# GT_pos_router.net
KiCad netlist of a schematic drawn in EAGLE
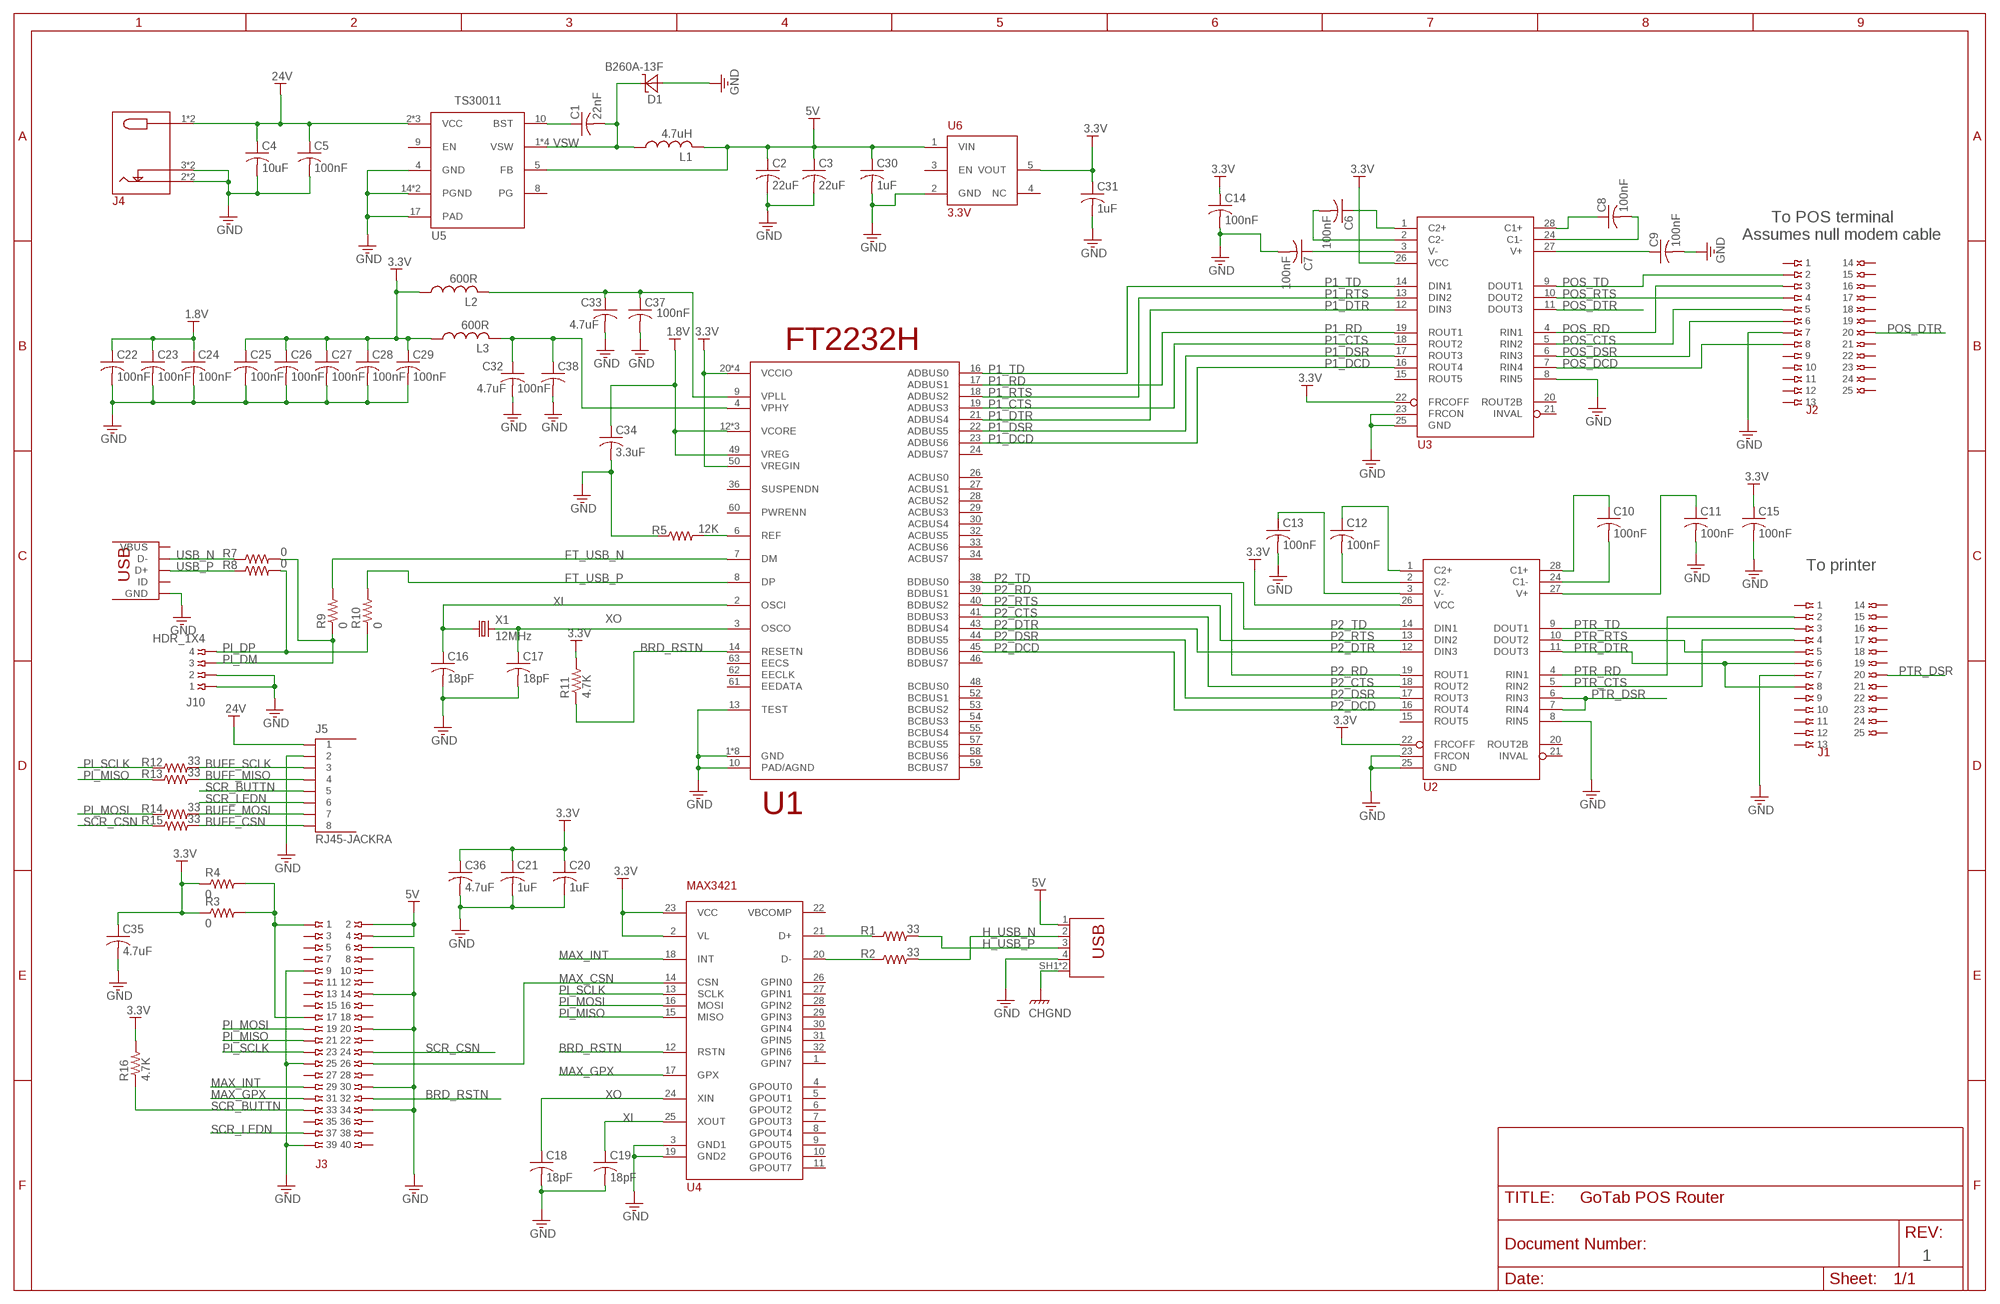
[diagram p0: schematic, sheet 1]

(export (version "E")
  (design (tool "Eeschema 10.0.6"))
  (components
    (comp (ref "C1")
      (value "22nF")
      (footprint "eagle-import:CAPC100X50X55L25N")
      (fields (field (name "VOLTAGE") "16V"))
      (libsource (lib "eagle-import") (part "C0402-22NF-16V-10-X7R"))
    )
    (comp (ref "C2")
      (value "22uF")
      (footprint "eagle-import:CAPC3216X85L50N")
      (fields (field (name "VOLTAGE") "25V"))
      (libsource (lib "eagle-import") (part "C1206-22UF-25V-20-X5R"))
    )
    (comp (ref "C3")
      (value "22uF")
      (footprint "eagle-import:CAPC3216X85L50N")
      (fields (field (name "VOLTAGE") "25V"))
      (libsource (lib "eagle-import") (part "C1206-22UF-25V-20-X5R"))
    )
    (comp (ref "C4")
      (value "10uF")
      (footprint "eagle-import:CAPC3216X85L50N")
      (fields (field (name "VOLTAGE") "35V"))
      (libsource (lib "eagle-import") (part "C1206-10UF-35V-10-X5R"))
    )
    (comp (ref "C5")
      (value "100nF")
      (footprint "eagle-import:CAPC1608X87L35N")
      (fields (field (name "VOLTAGE") "50V"))
      (libsource (lib "eagle-import") (part "C0603-100NF-50V-5-X7R"))
    )
    (comp (ref "C6")
      (value "100nF")
      (footprint "eagle-import:CAPC1608X87L35N")
      (fields (field (name "VOLTAGE") "50V"))
      (libsource (lib "eagle-import") (part "C0603-100NF-50V-5-X7R"))
    )
    (comp (ref "C7")
      (value "100nF")
      (footprint "eagle-import:CAPC1608X87L35N")
      (fields (field (name "VOLTAGE") "50V"))
      (libsource (lib "eagle-import") (part "C0603-100NF-50V-5-X7R"))
    )
    (comp (ref "C8")
      (value "100nF")
      (footprint "eagle-import:CAPC1608X87L35N")
      (fields (field (name "VOLTAGE") "50V"))
      (libsource (lib "eagle-import") (part "C0603-100NF-50V-5-X7R"))
    )
    (comp (ref "C9")
      (value "100nF")
      (footprint "eagle-import:CAPC1608X87L35N")
      (fields (field (name "VOLTAGE") "50V"))
      (libsource (lib "eagle-import") (part "C0603-100NF-50V-5-X7R"))
    )
    (comp (ref "C10")
      (value "100nF")
      (footprint "eagle-import:CAPC1608X87L35N")
      (fields (field (name "VOLTAGE") "50V"))
      (libsource (lib "eagle-import") (part "C0603-100NF-50V-5-X7R"))
    )
    (comp (ref "C11")
      (value "100nF")
      (footprint "eagle-import:CAPC1608X87L35N")
      (fields (field (name "VOLTAGE") "50V"))
      (libsource (lib "eagle-import") (part "C0603-100NF-50V-5-X7R"))
    )
    (comp (ref "C12")
      (value "100nF")
      (footprint "eagle-import:CAPC1608X87L35N")
      (fields (field (name "VOLTAGE") "50V"))
      (libsource (lib "eagle-import") (part "C0603-100NF-50V-5-X7R"))
    )
    (comp (ref "C13")
      (value "100nF")
      (footprint "eagle-import:CAPC1608X87L35N")
      (fields (field (name "VOLTAGE") "50V"))
      (libsource (lib "eagle-import") (part "C0603-100NF-50V-5-X7R"))
    )
    (comp (ref "C14")
      (value "100nF")
      (footprint "eagle-import:CAPC1608X87L35N")
      (fields (field (name "VOLTAGE") "50V"))
      (libsource (lib "eagle-import") (part "C0603-100NF-50V-5-X7R"))
    )
    (comp (ref "C15")
      (value "100nF")
      (footprint "eagle-import:CAPC1608X87L35N")
      (fields (field (name "VOLTAGE") "50V"))
      (libsource (lib "eagle-import") (part "C0603-100NF-50V-5-X7R"))
    )
    (comp (ref "C16")
      (value "18pF")
      (footprint "eagle-import:CAPC100X50X55L25N")
      (fields (field (name "VOLTAGE") "50V"))
      (libsource (lib "eagle-import") (part "C0402-18PF-50V-5-NPO"))
    )
    (comp (ref "C17")
      (value "18pF")
      (footprint "eagle-import:CAPC100X50X55L25N")
      (fields (field (name "VOLTAGE") "50V"))
      (libsource (lib "eagle-import") (part "C0402-18PF-50V-5-NPO"))
    )
    (comp (ref "C18")
      (value "18pF")
      (footprint "eagle-import:CAPC100X50X55L25N")
      (fields (field (name "VOLTAGE") "50V"))
      (libsource (lib "eagle-import") (part "C0402-18PF-50V-5-NPO"))
    )
    (comp (ref "C19")
      (value "18pF")
      (footprint "eagle-import:CAPC100X50X55L25N")
      (fields (field (name "VOLTAGE") "50V"))
      (libsource (lib "eagle-import") (part "C0402-18PF-50V-5-NPO"))
    )
    (comp (ref "C20")
      (value "1uF")
      (footprint "eagle-import:CAPC1608X87L35N")
      (fields (field (name "VOLTAGE") "16V"))
      (libsource (lib "eagle-import") (part "C0603-1UF-16V-10-X7R"))
    )
    (comp (ref "C21")
      (value "1uF")
      (footprint "eagle-import:CAPC1608X87L35N")
      (fields (field (name "VOLTAGE") "16V"))
      (libsource (lib "eagle-import") (part "C0603-1UF-16V-10-X7R"))
    )
    (comp (ref "C22")
      (value "100nF")
      (footprint "eagle-import:CAPC100X50X55L25N")
      (fields (field (name "VOLTAGE") "16V"))
      (libsource (lib "eagle-import") (part "C0402-100NF-16V-10-X7R"))
    )
    (comp (ref "C23")
      (value "100nF")
      (footprint "eagle-import:CAPC100X50X55L25N")
      (fields (field (name "VOLTAGE") "16V"))
      (libsource (lib "eagle-import") (part "C0402-100NF-16V-10-X7R"))
    )
    (comp (ref "C24")
      (value "100nF")
      (footprint "eagle-import:CAPC100X50X55L25N")
      (fields (field (name "VOLTAGE") "16V"))
      (libsource (lib "eagle-import") (part "C0402-100NF-16V-10-X7R"))
    )
    (comp (ref "C25")
      (value "100nF")
      (footprint "eagle-import:CAPC100X50X55L25N")
      (fields (field (name "VOLTAGE") "16V"))
      (libsource (lib "eagle-import") (part "C0402-100NF-16V-10-X7R"))
    )
    (comp (ref "C26")
      (value "100nF")
      (footprint "eagle-import:CAPC100X50X55L25N")
      (fields (field (name "VOLTAGE") "16V"))
      (libsource (lib "eagle-import") (part "C0402-100NF-16V-10-X7R"))
    )
    (comp (ref "C27")
      (value "100nF")
      (footprint "eagle-import:CAPC100X50X55L25N")
      (fields (field (name "VOLTAGE") "16V"))
      (libsource (lib "eagle-import") (part "C0402-100NF-16V-10-X7R"))
    )
    (comp (ref "C28")
      (value "100nF")
      (footprint "eagle-import:CAPC100X50X55L25N")
      (fields (field (name "VOLTAGE") "16V"))
      (libsource (lib "eagle-import") (part "C0402-100NF-16V-10-X7R"))
    )
    (comp (ref "C29")
      (value "100nF")
      (footprint "eagle-import:CAPC100X50X55L25N")
      (fields (field (name "VOLTAGE") "16V"))
      (libsource (lib "eagle-import") (part "C0402-100NF-16V-10-X7R"))
    )
    (comp (ref "C30")
      (value "1uF")
      (footprint "eagle-import:CAPC1608X87L35N")
      (fields (field (name "VOLTAGE") "16V"))
      (libsource (lib "eagle-import") (part "C0603-1UF-16V-10-X7R"))
    )
    (comp (ref "C31")
      (value "1uF")
      (footprint "eagle-import:CAPC1608X87L35N")
      (fields (field (name "VOLTAGE") "16V"))
      (libsource (lib "eagle-import") (part "C0603-1UF-16V-10-X7R"))
    )
    (comp (ref "C32")
      (value "4.7uF")
      (footprint "eagle-import:CAPC2012X140L50N")
      (fields (field (name "VOLTAGE") "10V"))
      (libsource (lib "eagle-import") (part "C0805-4.7UF-10V-10-X7R"))
    )
    (comp (ref "C33")
      (value "4.7uF")
      (footprint "eagle-import:CAPC2012X140L50N")
      (fields (field (name "VOLTAGE") "10V"))
      (libsource (lib "eagle-import") (part "C0805-4.7UF-10V-10-X7R"))
    )
    (comp (ref "C34")
      (value "3.3uF")
      (footprint "eagle-import:CAPC1608X87L35N")
      (fields (field (name "VOLTAGE") "6.3V"))
      (libsource (lib "eagle-import") (part "C0603-3.3UF-6.3V-10-X5R"))
    )
    (comp (ref "C35")
      (value "4.7uF")
      (footprint "eagle-import:CAPC2012X140L50N")
      (fields (field (name "VOLTAGE") "10V"))
      (libsource (lib "eagle-import") (part "C0805-4.7UF-10V-10-X7R"))
    )
    (comp (ref "C36")
      (value "4.7uF")
      (footprint "eagle-import:CAPC2012X140L50N")
      (fields (field (name "VOLTAGE") "10V"))
      (libsource (lib "eagle-import") (part "C0805-4.7UF-10V-10-X7R"))
    )
    (comp (ref "C37")
      (value "100nF")
      (footprint "eagle-import:CAPC100X50X55L25N")
      (fields (field (name "VOLTAGE") "16V"))
      (libsource (lib "eagle-import") (part "C0402-100NF-16V-10-X7R"))
    )
    (comp (ref "C38")
      (value "100nF")
      (footprint "eagle-import:CAPC100X50X55L25N")
      (fields (field (name "VOLTAGE") "16V"))
      (libsource (lib "eagle-import") (part "C0402-100NF-16V-10-X7R"))
    )
    (comp (ref "D1")
      (value "B260A-13F")
      (footprint "eagle-import:SODFL430X260X240L114X145N")
      (libsource (lib "eagle-import") (part "B260A-13F"))
    )
    (comp (ref "J1")
      (value "DB25-RA-MALE")
      (footprint "eagle-import:DB25-RA-MALE")
      (libsource (lib "eagle-import") (part "DB25-RA-MALE"))
    )
    (comp (ref "J2")
      (value "DB25-RA-FEMALE")
      (footprint "eagle-import:DB25-RA-FEMALE")
      (libsource (lib "eagle-import") (part "DB25-RA-FEMALE"))
    )
    (comp (ref "J3")
      (value "RPI_ZERO_HDR0.2_STACK")
      (footprint "eagle-import:RPI_ZERO_HDR")
      (libsource (lib "eagle-import") (part "RPI_ZERO_HDR0.2_STACK"))
    )
    (comp (ref "J4")
      (value "PWR_JACK_SW_NC")
      (footprint "eagle-import:PJ-202B")
      (libsource (lib "eagle-import") (part "PWR_JACK_SW_NC"))
    )
    (comp (ref "J5")
      (value "RJ45-JACKRA")
      (footprint "eagle-import:RJ45-RA")
      (libsource (lib "eagle-import") (part "RJ45-JACKRA"))
    )
    (comp (ref "J8")
      (value "USB-MICRO-B-SMT-FLG")
      (footprint "eagle-import:10118192-0001LF")
      (libsource (lib "eagle-import") (part "USB-MICRO-B-SMT-FLG"))
    )
    (comp (ref "J9")
      (value "USB-A-RECEPT-RA")
      (footprint "eagle-import:SS-52100-001")
      (libsource (lib "eagle-import") (part "USB-A-RECEPT-RA"))
    )
    (comp (ref "J10")
      (value "HDR_1X4")
      (footprint "eagle-import:HDR_0.1IN_1X4_1MM")
      (libsource (lib "eagle-import") (part "HDR_1X4"))
    )
    (comp (ref "L1")
      (value "4.7uH")
      (footprint "eagle-import:SRN4026")
      (libsource (lib "eagle-import") (part "L-SRN4026-4.7UH"))
    )
    (comp (ref "L2")
      (value "600R")
      (footprint "eagle-import:INDC100X50X55L25N")
      (libsource (lib "eagle-import") (part "L0402-600R-0.3A"))
    )
    (comp (ref "L3")
      (value "600R")
      (footprint "eagle-import:INDC100X50X55L25N")
      (libsource (lib "eagle-import") (part "L0402-600R-0.3A"))
    )
    (comp (ref "R1")
      (value "33")
      (footprint "eagle-import:RESC1005X40L25N")
      (fields (field (name "POWER") "1/16W"))
      (libsource (lib "eagle-import") (part "R0402-33-1/16W/-1"))
    )
    (comp (ref "R2")
      (value "33")
      (footprint "eagle-import:RESC1005X40L25N")
      (fields (field (name "POWER") "1/16W"))
      (libsource (lib "eagle-import") (part "R0402-33-1/16W/-1"))
    )
    (comp (ref "R3")
      (value "0")
      (footprint "eagle-import:RESC1005X40L25N")
      (fields (field (name "POWER") "1/16W"))
      (libsource (lib "eagle-import") (part "R0402-0-1/16W"))
    )
    (comp (ref "R4")
      (value "0")
      (footprint "eagle-import:RESC1005X40L25N")
      (fields (field (name "POWER") "1/16W"))
      (libsource (lib "eagle-import") (part "R0402-0-1/16W"))
    )
    (comp (ref "R5")
      (value "12K")
      (footprint "eagle-import:RESC1005X40L25N")
      (fields (field (name "POWER") "1/16W"))
      (libsource (lib "eagle-import") (part "R0402-12K-1/16W-1"))
    )
    (comp (ref "R7")
      (value "0")
      (footprint "eagle-import:RESC1005X40L25N")
      (fields (field (name "POWER") "1/16W"))
      (libsource (lib "eagle-import") (part "R0402-0-1/16W"))
    )
    (comp (ref "R8")
      (value "0")
      (footprint "eagle-import:RESC1005X40L25N")
      (fields (field (name "POWER") "1/16W"))
      (libsource (lib "eagle-import") (part "R0402-0-1/16W"))
    )
    (comp (ref "R9")
      (value "0")
      (footprint "eagle-import:RESC1005X40L25N")
      (fields (field (name "POWER") "1/16W"))
      (libsource (lib "eagle-import") (part "R0402-0-1/16W"))
    )
    (comp (ref "R10")
      (value "0")
      (footprint "eagle-import:RESC1005X40L25N")
      (fields (field (name "POWER") "1/16W"))
      (libsource (lib "eagle-import") (part "R0402-0-1/16W"))
    )
    (comp (ref "R11")
      (value "4.7K")
      (footprint "eagle-import:RESC1005X40L25N")
      (fields (field (name "POWER") "1/16W"))
      (libsource (lib "eagle-import") (part "R0402-4.7K-1/16W-1"))
    )
    (comp (ref "R12")
      (value "33")
      (footprint "eagle-import:RESC1005X40L25N")
      (fields (field (name "POWER") "1/16W"))
      (libsource (lib "eagle-import") (part "R0402-33-1/16W/-1"))
    )
    (comp (ref "R13")
      (value "33")
      (footprint "eagle-import:RESC1005X40L25N")
      (fields (field (name "POWER") "1/16W"))
      (libsource (lib "eagle-import") (part "R0402-33-1/16W/-1"))
    )
    (comp (ref "R14")
      (value "33")
      (footprint "eagle-import:RESC1005X40L25N")
      (fields (field (name "POWER") "1/16W"))
      (libsource (lib "eagle-import") (part "R0402-33-1/16W/-1"))
    )
    (comp (ref "R15")
      (value "33")
      (footprint "eagle-import:RESC1005X40L25N")
      (fields (field (name "POWER") "1/16W"))
      (libsource (lib "eagle-import") (part "R0402-33-1/16W/-1"))
    )
    (comp (ref "R16")
      (value "4.7K")
      (footprint "eagle-import:RESC1005X40L25N")
      (fields (field (name "POWER") "1/16W"))
      (libsource (lib "eagle-import") (part "R0402-4.7K-1/16W-1"))
    )
    (comp (ref "U1")
      (value "FT2232H")
      (footprint "eagle-import:LQFP64P050_120X120X160N")
      (libsource (lib "eagle-import") (part "FT2232H"))
    )
    (comp (ref "U2")
      (value "MAX3243ST-EB")
      (footprint "eagle-import:TSSOP28")
      (libsource (lib "eagle-import") (part "MAX3243ST-EB"))
    )
    (comp (ref "U3")
      (value "MAX3243ST-EB")
      (footprint "eagle-import:TSSOP28")
      (libsource (lib "eagle-import") (part "MAX3243ST-EB"))
    )
    (comp (ref "U4")
      (value "MAX3421")
      (footprint "eagle-import:TQFP32P050_50X50X120N")
      (libsource (lib "eagle-import") (part "MAX3421"))
    )
    (comp (ref "U5")
      (value "TS30011")
      (footprint "eagle-import:QFN16P05_3X3X10T17X17N")
      (libsource (lib "eagle-import") (part "TS30011"))
    )
    (comp (ref "U6")
      (value "3.3V")
      (footprint "eagle-import:SOT23-5P95_280X160L40X40N")
      (libsource (lib "eagle-import") (part "MIC5504"))
    )
    (comp (ref "X1")
      (value "12MHz")
      (footprint "eagle-import:ABLS2")
      (libsource (lib "eagle-import") (part "ABLS2-12M"))
    )
  )
  (nets
    (net (code "1") (name "/BRD_RSTN") (class "Default")
      (node (ref "J3") (pin "32") (pinfunction "32_32") (pintype "passive"))
      (node (ref "R11") (pin "1") (pinfunction "1_1") (pintype "passive"))
      (node (ref "U1") (pin "14") (pinfunction "RESETN_14") (pintype "bidirectional"))
      (node (ref "U4") (pin "12") (pinfunction "RSTN_12") (pintype "input"))
    )
    (net (code "2") (name "/BUFF_CSN") (class "Default")
      (node (ref "J5") (pin "8") (pinfunction "8_8") (pintype "passive"))
      (node (ref "R15") (pin "2") (pinfunction "2_2") (pintype "passive"))
    )
    (net (code "3") (name "/BUFF_MISO") (class "Default")
      (node (ref "J5") (pin "4") (pinfunction "4_4") (pintype "passive"))
      (node (ref "R13") (pin "2") (pinfunction "2_2") (pintype "passive"))
    )
    (net (code "4") (name "/BUFF_MOSI") (class "Default")
      (node (ref "J5") (pin "7") (pinfunction "7_7") (pintype "passive"))
      (node (ref "R14") (pin "2") (pinfunction "2_2") (pintype "passive"))
    )
    (net (code "5") (name "/BUFF_SCLK") (class "Default")
      (node (ref "J5") (pin "3") (pinfunction "3_3") (pintype "passive"))
      (node (ref "R12") (pin "2") (pinfunction "2_2") (pintype "passive"))
    )
    (net (code "6") (name "/FT_USB_N") (class "Default")
      (node (ref "R9") (pin "2") (pinfunction "2_2") (pintype "passive"))
      (node (ref "U1") (pin "7") (pinfunction "DM_7") (pintype "bidirectional"))
    )
    (net (code "7") (name "/FT_USB_P") (class "Default")
      (node (ref "R10") (pin "2") (pinfunction "2_2") (pintype "passive"))
      (node (ref "U1") (pin "8") (pinfunction "DP_8") (pintype "bidirectional"))
    )
    (net (code "8") (name "/H_USB_N") (class "Default")
      (node (ref "J9") (pin "2") (pinfunction "D-_2") (pintype "bidirectional"))
      (node (ref "R2") (pin "2") (pinfunction "2_2") (pintype "passive"))
    )
    (net (code "9") (name "/H_USB_P") (class "Default")
      (node (ref "J9") (pin "3") (pinfunction "D+_3") (pintype "bidirectional"))
      (node (ref "R1") (pin "2") (pinfunction "2_2") (pintype "passive"))
    )
    (net (code "10") (name "/MAX_CSN") (class "Default")
      (node (ref "J3") (pin "26") (pinfunction "26_26") (pintype "passive"))
      (node (ref "U4") (pin "14") (pinfunction "CSN_14") (pintype "input"))
    )
    (net (code "11") (name "/MAX_GPX") (class "Default")
      (node (ref "J3") (pin "31") (pinfunction "31_31") (pintype "passive"))
      (node (ref "U4") (pin "17") (pinfunction "GPX_17") (pintype "output"))
    )
    (net (code "12") (name "/MAX_INT") (class "Default")
      (node (ref "J3") (pin "29") (pinfunction "29_29") (pintype "passive"))
      (node (ref "U4") (pin "18") (pinfunction "INT_18") (pintype "output"))
    )
    (net (code "13") (name "/P1_CTS") (class "Default")
      (node (ref "U1") (pin "19") (pinfunction "ADBUS3_19") (pintype "bidirectional"))
      (node (ref "U3") (pin "18") (pinfunction "ROUT2_18") (pintype "output"))
    )
    (net (code "14") (name "/P1_DCD") (class "Default")
      (node (ref "U1") (pin "23") (pinfunction "ADBUS6_23") (pintype "bidirectional"))
      (node (ref "U3") (pin "16") (pinfunction "ROUT4_16") (pintype "output"))
    )
    (net (code "15") (name "/P1_DSR") (class "Default")
      (node (ref "U1") (pin "22") (pinfunction "ADBUS5_22") (pintype "bidirectional"))
      (node (ref "U3") (pin "17") (pinfunction "ROUT3_17") (pintype "output"))
    )
    (net (code "16") (name "/P1_DTR") (class "Default")
      (node (ref "U1") (pin "21") (pinfunction "ADBUS4_21") (pintype "bidirectional"))
      (node (ref "U3") (pin "12") (pinfunction "DIN3_12") (pintype "bidirectional"))
    )
    (net (code "17") (name "/P1_RD") (class "Default")
      (node (ref "U1") (pin "17") (pinfunction "ADBUS1_17") (pintype "bidirectional"))
      (node (ref "U3") (pin "19") (pinfunction "ROUT1_19") (pintype "output"))
    )
    (net (code "18") (name "/P1_RTS") (class "Default")
      (node (ref "U1") (pin "18") (pinfunction "ADBUS2_18") (pintype "bidirectional"))
      (node (ref "U3") (pin "13") (pinfunction "DIN2_13") (pintype "bidirectional"))
    )
    (net (code "19") (name "/P1_TD") (class "Default")
      (node (ref "U1") (pin "16") (pinfunction "ADBUS0_16") (pintype "bidirectional"))
      (node (ref "U3") (pin "14") (pinfunction "DIN1_14") (pintype "bidirectional"))
    )
    (net (code "20") (name "/P2_CTS") (class "Default")
      (node (ref "U1") (pin "41") (pinfunction "BDBUS3_41") (pintype "bidirectional"))
      (node (ref "U2") (pin "18") (pinfunction "ROUT2_18") (pintype "output"))
    )
    (net (code "21") (name "/P2_DCD") (class "Default")
      (node (ref "U1") (pin "45") (pinfunction "BDBUS6_45") (pintype "bidirectional"))
      (node (ref "U2") (pin "16") (pinfunction "ROUT4_16") (pintype "output"))
    )
    (net (code "22") (name "/P2_DSR") (class "Default")
      (node (ref "U1") (pin "44") (pinfunction "BDBUS5_44") (pintype "bidirectional"))
      (node (ref "U2") (pin "17") (pinfunction "ROUT3_17") (pintype "output"))
    )
    (net (code "23") (name "/P2_DTR") (class "Default")
      (node (ref "U1") (pin "43") (pinfunction "BDBUS4_43") (pintype "bidirectional"))
      (node (ref "U2") (pin "12") (pinfunction "DIN3_12") (pintype "bidirectional"))
    )
    (net (code "24") (name "/P2_RD") (class "Default")
      (node (ref "U1") (pin "39") (pinfunction "BDBUS1_39") (pintype "bidirectional"))
      (node (ref "U2") (pin "19") (pinfunction "ROUT1_19") (pintype "output"))
    )
    (net (code "25") (name "/P2_RTS") (class "Default")
      (node (ref "U1") (pin "40") (pinfunction "BDBUS2_40") (pintype "bidirectional"))
      (node (ref "U2") (pin "13") (pinfunction "DIN2_13") (pintype "bidirectional"))
    )
    (net (code "26") (name "/P2_TD") (class "Default")
      (node (ref "U1") (pin "38") (pinfunction "BDBUS0_38") (pintype "bidirectional"))
      (node (ref "U2") (pin "14") (pinfunction "DIN1_14") (pintype "bidirectional"))
    )
    (net (code "27") (name "/PI_DM") (class "Default")
      (node (ref "J10") (pin "3") (pinfunction "3_3") (pintype "passive"))
      (node (ref "R7") (pin "2") (pinfunction "2_2") (pintype "passive"))
      (node (ref "R9") (pin "1") (pinfunction "1_1") (pintype "passive"))
    )
    (net (code "28") (name "/PI_DP") (class "Default")
      (node (ref "J10") (pin "4") (pinfunction "4_4") (pintype "passive"))
      (node (ref "R10") (pin "1") (pinfunction "1_1") (pintype "passive"))
      (node (ref "R8") (pin "2") (pinfunction "2_2") (pintype "passive"))
    )
    (net (code "29") (name "/PI_MISO") (class "Default")
      (node (ref "J3") (pin "21") (pinfunction "21_21") (pintype "passive"))
      (node (ref "R13") (pin "1") (pinfunction "1_1") (pintype "passive"))
      (node (ref "U4") (pin "15") (pinfunction "MISO_15") (pintype "output"))
    )
    (net (code "30") (name "/PI_MOSI") (class "Default")
      (node (ref "J3") (pin "19") (pinfunction "19_19") (pintype "passive"))
      (node (ref "R14") (pin "1") (pinfunction "1_1") (pintype "passive"))
      (node (ref "U4") (pin "16") (pinfunction "MOSI_16") (pintype "bidirectional"))
    )
    (net (code "31") (name "/PI_SCLK") (class "Default")
      (node (ref "J3") (pin "23") (pinfunction "23_23") (pintype "passive"))
      (node (ref "R12") (pin "1") (pinfunction "1_1") (pintype "passive"))
      (node (ref "U4") (pin "13") (pinfunction "SCLK_13") (pintype "input"))
    )
    (net (code "32") (name "/POS_CTS") (class "Default")
      (node (ref "J2") (pin "5") (pinfunction "5_5") (pintype "passive"))
      (node (ref "U3") (pin "5") (pinfunction "RIN2_5") (pintype "input"))
    )
    (net (code "33") (name "/POS_DCD") (class "Default")
      (node (ref "J2") (pin "8") (pinfunction "8_8") (pintype "passive"))
      (node (ref "U3") (pin "7") (pinfunction "RIN4_7") (pintype "input"))
    )
    (net (code "34") (name "/POS_DSR") (class "Default")
      (node (ref "J2") (pin "6") (pinfunction "6_6") (pintype "passive"))
      (node (ref "U3") (pin "6") (pinfunction "RIN3_6") (pintype "input"))
    )
    (net (code "35") (name "/POS_DTR") (class "Default")
      (node (ref "J2") (pin "20") (pinfunction "20_20") (pintype "passive"))
      (node (ref "U3") (pin "11") (pinfunction "DOUT3_11") (pintype "bidirectional"))
    )
    (net (code "36") (name "/POS_RD") (class "Default")
      (node (ref "J2") (pin "3") (pinfunction "3_3") (pintype "passive"))
      (node (ref "U3") (pin "4") (pinfunction "RIN1_4") (pintype "input"))
    )
    (net (code "37") (name "/POS_RTS") (class "Default")
      (node (ref "J2") (pin "4") (pinfunction "4_4") (pintype "passive"))
      (node (ref "U3") (pin "10") (pinfunction "DOUT2_10") (pintype "bidirectional"))
    )
    (net (code "38") (name "/POS_TD") (class "Default")
      (node (ref "J2") (pin "2") (pinfunction "2_2") (pintype "passive"))
      (node (ref "U3") (pin "9") (pinfunction "DOUT1_9") (pintype "bidirectional"))
    )
    (net (code "39") (name "/PTR_CTS") (class "Default")
      (node (ref "J1") (pin "4") (pinfunction "4_4") (pintype "passive"))
      (node (ref "U2") (pin "5") (pinfunction "RIN2_5") (pintype "input"))
    )
    (net (code "40") (name "/PTR_DSR") (class "Default")
      (node (ref "J1") (pin "20") (pinfunction "20_20") (pintype "passive"))
      (node (ref "U2") (pin "6") (pinfunction "RIN3_6") (pintype "input"))
      (node (ref "U2") (pin "7") (pinfunction "RIN4_7") (pintype "input"))
    )
    (net (code "41") (name "/PTR_DTR") (class "Default")
      (node (ref "J1") (pin "6") (pinfunction "6_6") (pintype "passive"))
      (node (ref "J1") (pin "8") (pinfunction "8_8") (pintype "passive"))
      (node (ref "U2") (pin "11") (pinfunction "DOUT3_11") (pintype "bidirectional"))
    )
    (net (code "42") (name "/PTR_RD") (class "Default")
      (node (ref "J1") (pin "2") (pinfunction "2_2") (pintype "passive"))
      (node (ref "U2") (pin "4") (pinfunction "RIN1_4") (pintype "input"))
    )
    (net (code "43") (name "/PTR_RTS") (class "Default")
      (node (ref "J1") (pin "5") (pinfunction "5_5") (pintype "passive"))
      (node (ref "U2") (pin "10") (pinfunction "DOUT2_10") (pintype "bidirectional"))
    )
    (net (code "44") (name "/PTR_TD") (class "Default")
      (node (ref "J1") (pin "3") (pinfunction "3_3") (pintype "passive"))
      (node (ref "U2") (pin "9") (pinfunction "DOUT1_9") (pintype "bidirectional"))
    )
    (net (code "45") (name "/SCR_BUTTN") (class "Default")
      (node (ref "J3") (pin "33") (pinfunction "33_33") (pintype "passive"))
      (node (ref "J5") (pin "5") (pinfunction "5_5") (pintype "passive"))
      (node (ref "R16") (pin "1") (pinfunction "1_1") (pintype "passive"))
    )
    (net (code "46") (name "/SCR_CSN") (class "Default")
      (node (ref "J3") (pin "24") (pinfunction "24_24") (pintype "passive"))
      (node (ref "R15") (pin "1") (pinfunction "1_1") (pintype "passive"))
    )
    (net (code "47") (name "/SCR_LEDN") (class "Default")
      (node (ref "J3") (pin "37") (pinfunction "37_37") (pintype "passive"))
      (node (ref "J5") (pin "6") (pinfunction "6_6") (pintype "passive"))
    )
    (net (code "48") (name "/USB_N") (class "Default")
      (node (ref "J8") (pin "2") (pinfunction "D-_2") (pintype "bidirectional"))
      (node (ref "R7") (pin "1") (pinfunction "1_1") (pintype "passive"))
    )
    (net (code "49") (name "/USB_P") (class "Default")
      (node (ref "J8") (pin "3") (pinfunction "D+_3") (pintype "bidirectional"))
      (node (ref "R8") (pin "1") (pinfunction "1_1") (pintype "passive"))
    )
    (net (code "50") (name "/VBCOMP") (class "Default")
      (node (ref "U4") (pin "22") (pinfunction "VBCOMP_22") (pintype "power_in"))
    )
    (net (code "51") (name "/VSW") (class "Default")
      (node (ref "C1") (pin "2") (pinfunction "2_2") (pintype "passive"))
      (node (ref "D1") (pin "C") (pinfunction "C_C") (pintype "passive"))
      (node (ref "L1") (pin "1") (pinfunction "1_1") (pintype "passive"))
      (node (ref "U5") (pin "1") (pinfunction "VSW_1") (pintype "power_in"))
      (node (ref "U5") (pin "12") (pinfunction "VSW_12") (pintype "power_in"))
      (node (ref "U5") (pin "13") (pinfunction "VSW_13") (pintype "power_in"))
      (node (ref "U5") (pin "16") (pinfunction "VSW_16") (pintype "power_in"))
    )
    (net (code "52") (name "/XI") (class "Default")
      (node (ref "C16") (pin "1") (pinfunction "1_1") (pintype "passive"))
      (node (ref "C19") (pin "1") (pinfunction "1_1") (pintype "passive"))
      (node (ref "U1") (pin "2") (pinfunction "OSCI_2") (pintype "bidirectional"))
      (node (ref "U4") (pin "25") (pinfunction "XOUT_25") (pintype "passive"))
      (node (ref "X1") (pin "1") (pinfunction "1_1") (pintype "passive"))
    )
    (net (code "53") (name "/XO") (class "Default")
      (node (ref "C17") (pin "1") (pinfunction "1_1") (pintype "passive"))
      (node (ref "C18") (pin "1") (pinfunction "1_1") (pintype "passive"))
      (node (ref "U1") (pin "3") (pinfunction "OSCO_3") (pintype "bidirectional"))
      (node (ref "U4") (pin "24") (pinfunction "XIN_24") (pintype "passive"))
      (node (ref "X1") (pin "2") (pinfunction "2_2") (pintype "passive"))
    )
    (net (code "54") (name "1.8V") (class "Default")
      (node (ref "C22") (pin "1") (pinfunction "1_1") (pintype "passive"))
      (node (ref "C23") (pin "1") (pinfunction "1_1") (pintype "passive"))
      (node (ref "C24") (pin "1") (pinfunction "1_1") (pintype "passive"))
      (node (ref "C34") (pin "1") (pinfunction "1_1") (pintype "passive"))
      (node (ref "U1") (pin "12") (pinfunction "VCORE_12") (pintype "bidirectional"))
      (node (ref "U1") (pin "37") (pinfunction "VCORE_37") (pintype "bidirectional"))
      (node (ref "U1") (pin "49") (pinfunction "VREG_49") (pintype "bidirectional"))
      (node (ref "U1") (pin "64") (pinfunction "VCORE_64") (pintype "bidirectional"))
    )
    (net (code "55") (name "3.3V") (class "Default")
      (node (ref "C14") (pin "1") (pinfunction "1_1") (pintype "passive"))
      (node (ref "C15") (pin "1") (pinfunction "1_1") (pintype "passive"))
      (node (ref "C20") (pin "1") (pinfunction "1_1") (pintype "passive"))
      (node (ref "C21") (pin "1") (pinfunction "1_1") (pintype "passive"))
      (node (ref "C25") (pin "1") (pinfunction "1_1") (pintype "passive"))
      (node (ref "C26") (pin "1") (pinfunction "1_1") (pintype "passive"))
      (node (ref "C27") (pin "1") (pinfunction "1_1") (pintype "passive"))
      (node (ref "C28") (pin "1") (pinfunction "1_1") (pintype "passive"))
      (node (ref "C29") (pin "1") (pinfunction "1_1") (pintype "passive"))
      (node (ref "C31") (pin "1") (pinfunction "1_1") (pintype "passive"))
      (node (ref "C35") (pin "1") (pinfunction "1_1") (pintype "passive"))
      (node (ref "C36") (pin "1") (pinfunction "1_1") (pintype "passive"))
      (node (ref "L2") (pin "1") (pinfunction "1_1") (pintype "passive"))
      (node (ref "L3") (pin "1") (pinfunction "1_1") (pintype "passive"))
      (node (ref "R11") (pin "2") (pinfunction "2_2") (pintype "passive"))
      (node (ref "R16") (pin "2") (pinfunction "2_2") (pintype "passive"))
      (node (ref "R3") (pin "1") (pinfunction "1_1") (pintype "passive"))
      (node (ref "R4") (pin "1") (pinfunction "1_1") (pintype "passive"))
      (node (ref "U1") (pin "20") (pinfunction "VCCIO_20") (pintype "bidirectional"))
      (node (ref "U1") (pin "31") (pinfunction "VCCIO_31") (pintype "bidirectional"))
      (node (ref "U1") (pin "42") (pinfunction "VCCIO_42") (pintype "bidirectional"))
      (node (ref "U1") (pin "50") (pinfunction "VREGIN_50") (pintype "bidirectional"))
      (node (ref "U1") (pin "56") (pinfunction "VCCIO_56") (pintype "bidirectional"))
      (node (ref "U2") (pin "22") (pinfunction "FRCOFF_22") (pintype "input"))
      (node (ref "U2") (pin "26") (pinfunction "VCC_26") (pintype "power_in"))
      (node (ref "U3") (pin "22") (pinfunction "FRCOFF_22") (pintype "input"))
      (node (ref "U3") (pin "26") (pinfunction "VCC_26") (pintype "power_in"))
      (node (ref "U4") (pin "2") (pinfunction "VL_2") (pintype "bidirectional"))
      (node (ref "U4") (pin "23") (pinfunction "VCC_23") (pintype "power_in"))
      (node (ref "U6") (pin "5") (pinfunction "VOUT_5") (pintype "bidirectional"))
    )
    (net (code "56") (name "5V") (class "Default")
      (node (ref "C2") (pin "1") (pinfunction "1_1") (pintype "passive"))
      (node (ref "C3") (pin "1") (pinfunction "1_1") (pintype "passive"))
      (node (ref "C30") (pin "1") (pinfunction "1_1") (pintype "passive"))
      (node (ref "J3") (pin "2") (pinfunction "2_2") (pintype "passive"))
      (node (ref "J3") (pin "4") (pinfunction "4_4") (pintype "passive"))
      (node (ref "J9") (pin "1") (pinfunction "VBUS_1") (pintype "bidirectional"))
      (node (ref "L1") (pin "2") (pinfunction "2_2") (pintype "passive"))
      (node (ref "U5") (pin "5") (pinfunction "FB_5") (pintype "passive"))
      (node (ref "U6") (pin "1") (pinfunction "VIN_1") (pintype "bidirectional"))
    )
    (net (code "57") (name "24V") (class "Default")
      (node (ref "C4") (pin "1") (pinfunction "1_1") (pintype "passive"))
      (node (ref "C5") (pin "1") (pinfunction "1_1") (pintype "passive"))
      (node (ref "J4") (pin "1") (pinfunction "1_1") (pintype "bidirectional"))
      (node (ref "J4") (pin "4") (pinfunction "1_4") (pintype "bidirectional"))
      (node (ref "J5") (pin "1") (pinfunction "1_1") (pintype "passive"))
      (node (ref "U5") (pin "11") (pinfunction "VCC_11") (pintype "power_in"))
      (node (ref "U5") (pin "2") (pinfunction "VCC_2") (pintype "power_in"))
      (node (ref "U5") (pin "3") (pinfunction "VCC_3") (pintype "power_in"))
    )
    (net (code "58") (name "CHGND") (class "Default")
      (node (ref "J9") (pin "SH1") (pinfunction "SHELL_SH1") (pintype "bidirectional"))
      (node (ref "J9") (pin "SH2") (pinfunction "SHELL_SH2") (pintype "bidirectional"))
    )
    (net (code "59") (name "GND") (class "Default")
      (node (ref "C11") (pin "2") (pinfunction "2_2") (pintype "passive"))
      (node (ref "C13") (pin "2") (pinfunction "2_2") (pintype "passive"))
      (node (ref "C14") (pin "2") (pinfunction "2_2") (pintype "passive"))
      (node (ref "C15") (pin "2") (pinfunction "2_2") (pintype "passive"))
      (node (ref "C16") (pin "2") (pinfunction "2_2") (pintype "passive"))
      (node (ref "C17") (pin "2") (pinfunction "2_2") (pintype "passive"))
      (node (ref "C18") (pin "2") (pinfunction "2_2") (pintype "passive"))
      (node (ref "C19") (pin "2") (pinfunction "2_2") (pintype "passive"))
      (node (ref "C2") (pin "2") (pinfunction "2_2") (pintype "passive"))
      (node (ref "C20") (pin "2") (pinfunction "2_2") (pintype "passive"))
      (node (ref "C21") (pin "2") (pinfunction "2_2") (pintype "passive"))
      (node (ref "C22") (pin "2") (pinfunction "2_2") (pintype "passive"))
      (node (ref "C23") (pin "2") (pinfunction "2_2") (pintype "passive"))
      (node (ref "C24") (pin "2") (pinfunction "2_2") (pintype "passive"))
      (node (ref "C25") (pin "2") (pinfunction "2_2") (pintype "passive"))
      (node (ref "C26") (pin "2") (pinfunction "2_2") (pintype "passive"))
      (node (ref "C27") (pin "2") (pinfunction "2_2") (pintype "passive"))
      (node (ref "C28") (pin "2") (pinfunction "2_2") (pintype "passive"))
      (node (ref "C29") (pin "2") (pinfunction "2_2") (pintype "passive"))
      (node (ref "C3") (pin "2") (pinfunction "2_2") (pintype "passive"))
      (node (ref "C30") (pin "2") (pinfunction "2_2") (pintype "passive"))
      (node (ref "C31") (pin "2") (pinfunction "2_2") (pintype "passive"))
      (node (ref "C32") (pin "2") (pinfunction "2_2") (pintype "passive"))
      (node (ref "C33") (pin "2") (pinfunction "2_2") (pintype "passive"))
      (node (ref "C34") (pin "2") (pinfunction "2_2") (pintype "passive"))
      (node (ref "C35") (pin "2") (pinfunction "2_2") (pintype "passive"))
      (node (ref "C36") (pin "2") (pinfunction "2_2") (pintype "passive"))
      (node (ref "C37") (pin "2") (pinfunction "2_2") (pintype "passive"))
      (node (ref "C38") (pin "2") (pinfunction "2_2") (pintype "passive"))
      (node (ref "C4") (pin "2") (pinfunction "2_2") (pintype "passive"))
      (node (ref "C5") (pin "2") (pinfunction "2_2") (pintype "passive"))
      (node (ref "C7") (pin "2") (pinfunction "2_2") (pintype "passive"))
      (node (ref "C9") (pin "2") (pinfunction "2_2") (pintype "passive"))
      (node (ref "D1") (pin "A") (pinfunction "A_A") (pintype "passive"))
      (node (ref "J1") (pin "7") (pinfunction "7_7") (pintype "passive"))
      (node (ref "J10") (pin "1") (pinfunction "1_1") (pintype "passive"))
      (node (ref "J10") (pin "2") (pinfunction "2_2") (pintype "passive"))
      (node (ref "J2") (pin "7") (pinfunction "7_7") (pintype "passive"))
      (node (ref "J3") (pin "14") (pinfunction "14_14") (pintype "passive"))
      (node (ref "J3") (pin "20") (pinfunction "20_20") (pintype "passive"))
      (node (ref "J3") (pin "25") (pinfunction "25_25") (pintype "passive"))
      (node (ref "J3") (pin "30") (pinfunction "30_30") (pintype "passive"))
      (node (ref "J3") (pin "34") (pinfunction "34_34") (pintype "passive"))
      (node (ref "J3") (pin "39") (pinfunction "39_39") (pintype "passive"))
      (node (ref "J3") (pin "6") (pinfunction "6_6") (pintype "passive"))
      (node (ref "J3") (pin "9") (pinfunction "9_9") (pintype "passive"))
      (node (ref "J4") (pin "2") (pinfunction "2_2") (pintype "bidirectional"))
      (node (ref "J4") (pin "3") (pinfunction "3_3") (pintype "bidirectional"))
      (node (ref "J4") (pin "5") (pinfunction "2_5") (pintype "bidirectional"))
      (node (ref "J4") (pin "6") (pinfunction "3_6") (pintype "bidirectional"))
      (node (ref "J5") (pin "2") (pinfunction "2_2") (pintype "passive"))
      (node (ref "J8") (pin "5") (pinfunction "GND_5") (pintype "bidirectional"))
      (node (ref "J9") (pin "4") (pinfunction "GND_4") (pintype "bidirectional"))
      (node (ref "R5") (pin "1") (pinfunction "1_1") (pintype "passive"))
      (node (ref "U1") (pin "1") (pinfunction "GND_1") (pintype "bidirectional"))
      (node (ref "U1") (pin "10") (pinfunction "PAD/AGND_10") (pintype "bidirectional"))
      (node (ref "U1") (pin "11") (pinfunction "GND_11") (pintype "bidirectional"))
      (node (ref "U1") (pin "13") (pinfunction "TEST_13") (pintype "bidirectional"))
      (node (ref "U1") (pin "15") (pinfunction "GND_15") (pintype "bidirectional"))
      (node (ref "U1") (pin "25") (pinfunction "GND_25") (pintype "bidirectional"))
      (node (ref "U1") (pin "35") (pinfunction "GND_35") (pintype "bidirectional"))
      (node (ref "U1") (pin "47") (pinfunction "GND_47") (pintype "bidirectional"))
      (node (ref "U1") (pin "5") (pinfunction "GND_5") (pintype "bidirectional"))
      (node (ref "U1") (pin "51") (pinfunction "GND_51") (pintype "bidirectional"))
      (node (ref "U2") (pin "23") (pinfunction "FRCON_23") (pintype "input"))
      (node (ref "U2") (pin "25") (pinfunction "GND_25") (pintype "power_in"))
      (node (ref "U2") (pin "8") (pinfunction "RIN5_8") (pintype "input"))
      (node (ref "U3") (pin "23") (pinfunction "FRCON_23") (pintype "input"))
      (node (ref "U3") (pin "25") (pinfunction "GND_25") (pintype "power_in"))
      (node (ref "U3") (pin "8") (pinfunction "RIN5_8") (pintype "input"))
      (node (ref "U4") (pin "19") (pinfunction "GND2_19") (pintype "power_in"))
      (node (ref "U4") (pin "3") (pinfunction "GND1_3") (pintype "power_in"))
      (node (ref "U5") (pin "14") (pinfunction "PGND_14") (pintype "power_in"))
      (node (ref "U5") (pin "15") (pinfunction "PGND_15") (pintype "power_in"))
      (node (ref "U5") (pin "17") (pinfunction "PAD_17") (pintype "power_in"))
      (node (ref "U5") (pin "4") (pinfunction "GND_4") (pintype "power_in"))
      (node (ref "U6") (pin "2") (pinfunction "GND_2") (pintype "bidirectional"))
    )
    (net (code "60") (name "Net-(J3-Pad1)") (class "Default")
      (node (ref "J3") (pin "1") (pinfunction "1_1") (pintype "passive"))
      (node (ref "J3") (pin "17") (pinfunction "17_17") (pintype "passive"))
      (node (ref "R3") (pin "2") (pinfunction "2_2") (pintype "passive"))
      (node (ref "R4") (pin "2") (pinfunction "2_2") (pintype "passive"))
    )
    (net (code "61") (name "Net-(U1-REF)") (class "Default")
      (node (ref "R5") (pin "2") (pinfunction "2_2") (pintype "passive"))
      (node (ref "U1") (pin "6") (pinfunction "REF_6") (pintype "bidirectional"))
    )
    (net (code "62") (name "Net-(U1-VPHY)") (class "Default")
      (node (ref "C32") (pin "1") (pinfunction "1_1") (pintype "passive"))
      (node (ref "C38") (pin "1") (pinfunction "1_1") (pintype "passive"))
      (node (ref "L3") (pin "2") (pinfunction "2_2") (pintype "passive"))
      (node (ref "U1") (pin "4") (pinfunction "VPHY_4") (pintype "bidirectional"))
    )
    (net (code "63") (name "Net-(U1-VPLL)") (class "Default")
      (node (ref "C33") (pin "1") (pinfunction "1_1") (pintype "passive"))
      (node (ref "C37") (pin "1") (pinfunction "1_1") (pintype "passive"))
      (node (ref "L2") (pin "2") (pinfunction "2_2") (pintype "passive"))
      (node (ref "U1") (pin "9") (pinfunction "VPLL_9") (pintype "bidirectional"))
    )
    (net (code "64") (name "Net-(U2-C1+)") (class "Default")
      (node (ref "C10") (pin "1") (pinfunction "1_1") (pintype "passive"))
      (node (ref "U2") (pin "28") (pinfunction "C1+_28") (pintype "passive"))
    )
    (net (code "65") (name "Net-(U2-C1-)") (class "Default")
      (node (ref "C10") (pin "2") (pinfunction "2_2") (pintype "passive"))
      (node (ref "U2") (pin "24") (pinfunction "C1-_24") (pintype "passive"))
    )
    (net (code "66") (name "Net-(U2-C2+)") (class "Default")
      (node (ref "C12") (pin "1") (pinfunction "1_1") (pintype "passive"))
      (node (ref "U2") (pin "1") (pinfunction "C2+_1") (pintype "passive"))
    )
    (net (code "67") (name "Net-(U2-C2-)") (class "Default")
      (node (ref "C12") (pin "2") (pinfunction "2_2") (pintype "passive"))
      (node (ref "U2") (pin "2") (pinfunction "C2-_2") (pintype "passive"))
    )
    (net (code "68") (name "Net-(U2-V+)") (class "Default")
      (node (ref "C11") (pin "1") (pinfunction "1_1") (pintype "passive"))
      (node (ref "U2") (pin "27") (pinfunction "V+_27") (pintype "bidirectional"))
    )
    (net (code "69") (name "Net-(U2-V-)") (class "Default")
      (node (ref "C13") (pin "1") (pinfunction "1_1") (pintype "passive"))
      (node (ref "U2") (pin "3") (pinfunction "V-_3") (pintype "power_in"))
    )
    (net (code "70") (name "Net-(U3-C1+)") (class "Default")
      (node (ref "C8") (pin "1") (pinfunction "1_1") (pintype "passive"))
      (node (ref "U3") (pin "28") (pinfunction "C1+_28") (pintype "passive"))
    )
    (net (code "71") (name "Net-(U3-C1-)") (class "Default")
      (node (ref "C8") (pin "2") (pinfunction "2_2") (pintype "passive"))
      (node (ref "U3") (pin "24") (pinfunction "C1-_24") (pintype "passive"))
    )
    (net (code "72") (name "Net-(U3-C2+)") (class "Default")
      (node (ref "C6") (pin "1") (pinfunction "1_1") (pintype "passive"))
      (node (ref "U3") (pin "1") (pinfunction "C2+_1") (pintype "passive"))
    )
    (net (code "73") (name "Net-(U3-C2-)") (class "Default")
      (node (ref "C6") (pin "2") (pinfunction "2_2") (pintype "passive"))
      (node (ref "U3") (pin "2") (pinfunction "C2-_2") (pintype "passive"))
    )
    (net (code "74") (name "Net-(U3-V+)") (class "Default")
      (node (ref "C9") (pin "1") (pinfunction "1_1") (pintype "passive"))
      (node (ref "U3") (pin "27") (pinfunction "V+_27") (pintype "bidirectional"))
    )
    (net (code "75") (name "Net-(U3-V-)") (class "Default")
      (node (ref "C7") (pin "1") (pinfunction "1_1") (pintype "passive"))
      (node (ref "U3") (pin "3") (pinfunction "V-_3") (pintype "power_in"))
    )
    (net (code "76") (name "Net-(U4-D+)") (class "Default")
      (node (ref "R1") (pin "1") (pinfunction "1_1") (pintype "passive"))
      (node (ref "U4") (pin "21") (pinfunction "D+_21") (pintype "bidirectional"))
    )
    (net (code "77") (name "Net-(U4-D-)") (class "Default")
      (node (ref "R2") (pin "1") (pinfunction "1_1") (pintype "passive"))
      (node (ref "U4") (pin "20") (pinfunction "D-_20") (pintype "bidirectional"))
    )
    (net (code "78") (name "Net-(U5-BST)") (class "Default")
      (node (ref "C1") (pin "1") (pinfunction "1_1") (pintype "passive"))
      (node (ref "U5") (pin "10") (pinfunction "BST_10") (pintype "passive"))
    )
    (net (code "79") (name "unconnected-(J1-Pad1)") (class "Default")
      (node (ref "J1") (pin "1") (pinfunction "1_1") (pintype "passive"))
    )
    (net (code "80") (name "unconnected-(J1-Pad9)") (class "Default")
      (node (ref "J1") (pin "9") (pinfunction "9_9") (pintype "passive"))
    )
    (net (code "81") (name "unconnected-(J1-Pad10)") (class "Default")
      (node (ref "J1") (pin "10") (pinfunction "10_10") (pintype "passive"))
    )
    (net (code "82") (name "unconnected-(J1-Pad11)") (class "Default")
      (node (ref "J1") (pin "11") (pinfunction "11_11") (pintype "passive"))
    )
    (net (code "83") (name "unconnected-(J1-Pad12)") (class "Default")
      (node (ref "J1") (pin "12") (pinfunction "12_12") (pintype "passive"))
    )
    (net (code "84") (name "unconnected-(J1-Pad13)") (class "Default")
      (node (ref "J1") (pin "13") (pinfunction "13_13") (pintype "passive"))
    )
    (net (code "85") (name "unconnected-(J1-Pad14)") (class "Default")
      (node (ref "J1") (pin "14") (pinfunction "14_14") (pintype "passive"))
    )
    (net (code "86") (name "unconnected-(J1-Pad15)") (class "Default")
      (node (ref "J1") (pin "15") (pinfunction "15_15") (pintype "passive"))
    )
    (net (code "87") (name "unconnected-(J1-Pad16)") (class "Default")
      (node (ref "J1") (pin "16") (pinfunction "16_16") (pintype "passive"))
    )
    (net (code "88") (name "unconnected-(J1-Pad17)") (class "Default")
      (node (ref "J1") (pin "17") (pinfunction "17_17") (pintype "passive"))
    )
    (net (code "89") (name "unconnected-(J1-Pad18)") (class "Default")
      (node (ref "J1") (pin "18") (pinfunction "18_18") (pintype "passive"))
    )
    (net (code "90") (name "unconnected-(J1-Pad19)") (class "Default")
      (node (ref "J1") (pin "19") (pinfunction "19_19") (pintype "passive"))
    )
    (net (code "91") (name "unconnected-(J1-Pad21)") (class "Default")
      (node (ref "J1") (pin "21") (pinfunction "21_21") (pintype "passive"))
    )
    (net (code "92") (name "unconnected-(J1-Pad22)") (class "Default")
      (node (ref "J1") (pin "22") (pinfunction "22_22") (pintype "passive"))
    )
    (net (code "93") (name "unconnected-(J1-Pad23)") (class "Default")
      (node (ref "J1") (pin "23") (pinfunction "23_23") (pintype "passive"))
    )
    (net (code "94") (name "unconnected-(J1-Pad24)") (class "Default")
      (node (ref "J1") (pin "24") (pinfunction "24_24") (pintype "passive"))
    )
    (net (code "95") (name "unconnected-(J1-Pad25)") (class "Default")
      (node (ref "J1") (pin "25") (pinfunction "25_25") (pintype "passive"))
    )
    (net (code "96") (name "unconnected-(J2-Pad1)") (class "Default")
      (node (ref "J2") (pin "1") (pinfunction "1_1") (pintype "passive"))
    )
    (net (code "97") (name "unconnected-(J2-Pad9)") (class "Default")
      (node (ref "J2") (pin "9") (pinfunction "9_9") (pintype "passive"))
    )
    (net (code "98") (name "unconnected-(J2-Pad10)") (class "Default")
      (node (ref "J2") (pin "10") (pinfunction "10_10") (pintype "passive"))
    )
    (net (code "99") (name "unconnected-(J2-Pad11)") (class "Default")
      (node (ref "J2") (pin "11") (pinfunction "11_11") (pintype "passive"))
    )
    (net (code "100") (name "unconnected-(J2-Pad12)") (class "Default")
      (node (ref "J2") (pin "12") (pinfunction "12_12") (pintype "passive"))
    )
    (net (code "101") (name "unconnected-(J2-Pad13)") (class "Default")
      (node (ref "J2") (pin "13") (pinfunction "13_13") (pintype "passive"))
    )
    (net (code "102") (name "unconnected-(J2-Pad14)") (class "Default")
      (node (ref "J2") (pin "14") (pinfunction "14_14") (pintype "passive"))
    )
    (net (code "103") (name "unconnected-(J2-Pad15)") (class "Default")
      (node (ref "J2") (pin "15") (pinfunction "15_15") (pintype "passive"))
    )
    (net (code "104") (name "unconnected-(J2-Pad16)") (class "Default")
      (node (ref "J2") (pin "16") (pinfunction "16_16") (pintype "passive"))
    )
    (net (code "105") (name "unconnected-(J2-Pad17)") (class "Default")
      (node (ref "J2") (pin "17") (pinfunction "17_17") (pintype "passive"))
    )
    (net (code "106") (name "unconnected-(J2-Pad18)") (class "Default")
      (node (ref "J2") (pin "18") (pinfunction "18_18") (pintype "passive"))
    )
    (net (code "107") (name "unconnected-(J2-Pad19)") (class "Default")
      (node (ref "J2") (pin "19") (pinfunction "19_19") (pintype "passive"))
    )
    (net (code "108") (name "unconnected-(J2-Pad21)") (class "Default")
      (node (ref "J2") (pin "21") (pinfunction "21_21") (pintype "passive"))
    )
    (net (code "109") (name "unconnected-(J2-Pad22)") (class "Default")
      (node (ref "J2") (pin "22") (pinfunction "22_22") (pintype "passive"))
    )
    (net (code "110") (name "unconnected-(J2-Pad23)") (class "Default")
      (node (ref "J2") (pin "23") (pinfunction "23_23") (pintype "passive"))
    )
    (net (code "111") (name "unconnected-(J2-Pad24)") (class "Default")
      (node (ref "J2") (pin "24") (pinfunction "24_24") (pintype "passive"))
    )
    (net (code "112") (name "unconnected-(J2-Pad25)") (class "Default")
      (node (ref "J2") (pin "25") (pinfunction "25_25") (pintype "passive"))
    )
    (net (code "113") (name "unconnected-(J3-Pad3)") (class "Default")
      (node (ref "J3") (pin "3") (pinfunction "3_3") (pintype "passive"))
    )
    (net (code "114") (name "unconnected-(J3-Pad5)") (class "Default")
      (node (ref "J3") (pin "5") (pinfunction "5_5") (pintype "passive"))
    )
    (net (code "115") (name "unconnected-(J3-Pad7)") (class "Default")
      (node (ref "J3") (pin "7") (pinfunction "7_7") (pintype "passive"))
    )
    (net (code "116") (name "unconnected-(J3-Pad8)") (class "Default")
      (node (ref "J3") (pin "8") (pinfunction "8_8") (pintype "passive"))
    )
    (net (code "117") (name "unconnected-(J3-Pad10)") (class "Default")
      (node (ref "J3") (pin "10") (pinfunction "10_10") (pintype "passive"))
    )
    (net (code "118") (name "unconnected-(J3-Pad11)") (class "Default")
      (node (ref "J3") (pin "11") (pinfunction "11_11") (pintype "passive"))
    )
    (net (code "119") (name "unconnected-(J3-Pad12)") (class "Default")
      (node (ref "J3") (pin "12") (pinfunction "12_12") (pintype "passive"))
    )
    (net (code "120") (name "unconnected-(J3-Pad13)") (class "Default")
      (node (ref "J3") (pin "13") (pinfunction "13_13") (pintype "passive"))
    )
    (net (code "121") (name "unconnected-(J3-Pad15)") (class "Default")
      (node (ref "J3") (pin "15") (pinfunction "15_15") (pintype "passive"))
    )
    (net (code "122") (name "unconnected-(J3-Pad16)") (class "Default")
      (node (ref "J3") (pin "16") (pinfunction "16_16") (pintype "passive"))
    )
    (net (code "123") (name "unconnected-(J3-Pad18)") (class "Default")
      (node (ref "J3") (pin "18") (pinfunction "18_18") (pintype "passive"))
    )
    (net (code "124") (name "unconnected-(J3-Pad22)") (class "Default")
      (node (ref "J3") (pin "22") (pinfunction "22_22") (pintype "passive"))
    )
    (net (code "125") (name "unconnected-(J3-Pad27)") (class "Default")
      (node (ref "J3") (pin "27") (pinfunction "27_27") (pintype "passive"))
    )
    (net (code "126") (name "unconnected-(J3-Pad28)") (class "Default")
      (node (ref "J3") (pin "28") (pinfunction "28_28") (pintype "passive"))
    )
    (net (code "127") (name "unconnected-(J3-Pad35)") (class "Default")
      (node (ref "J3") (pin "35") (pinfunction "35_35") (pintype "passive"))
    )
    (net (code "128") (name "unconnected-(J3-Pad36)") (class "Default")
      (node (ref "J3") (pin "36") (pinfunction "36_36") (pintype "passive"))
    )
    (net (code "129") (name "unconnected-(J3-Pad38)") (class "Default")
      (node (ref "J3") (pin "38") (pinfunction "38_38") (pintype "passive"))
    )
    (net (code "130") (name "unconnected-(J3-Pad40)") (class "Default")
      (node (ref "J3") (pin "40") (pinfunction "40_40") (pintype "passive"))
    )
    (net (code "131") (name "unconnected-(J8-ID-Pad4)") (class "Default")
      (node (ref "J8") (pin "4") (pinfunction "ID_4") (pintype "bidirectional"))
    )
    (net (code "132") (name "unconnected-(J8-VBUS-Pad1)") (class "Default")
      (node (ref "J8") (pin "1") (pinfunction "VBUS_1") (pintype "bidirectional"))
    )
    (net (code "133") (name "unconnected-(U1-ACBUS0-Pad26)") (class "Default")
      (node (ref "U1") (pin "26") (pinfunction "ACBUS0_26") (pintype "bidirectional"))
    )
    (net (code "134") (name "unconnected-(U1-ACBUS1-Pad27)") (class "Default")
      (node (ref "U1") (pin "27") (pinfunction "ACBUS1_27") (pintype "bidirectional"))
    )
    (net (code "135") (name "unconnected-(U1-ACBUS2-Pad28)") (class "Default")
      (node (ref "U1") (pin "28") (pinfunction "ACBUS2_28") (pintype "bidirectional"))
    )
    (net (code "136") (name "unconnected-(U1-ACBUS3-Pad29)") (class "Default")
      (node (ref "U1") (pin "29") (pinfunction "ACBUS3_29") (pintype "bidirectional"))
    )
    (net (code "137") (name "unconnected-(U1-ACBUS4-Pad30)") (class "Default")
      (node (ref "U1") (pin "30") (pinfunction "ACBUS4_30") (pintype "bidirectional"))
    )
    (net (code "138") (name "unconnected-(U1-ACBUS5-Pad32)") (class "Default")
      (node (ref "U1") (pin "32") (pinfunction "ACBUS5_32") (pintype "bidirectional"))
    )
    (net (code "139") (name "unconnected-(U1-ACBUS6-Pad33)") (class "Default")
      (node (ref "U1") (pin "33") (pinfunction "ACBUS6_33") (pintype "bidirectional"))
    )
    (net (code "140") (name "unconnected-(U1-ACBUS7-Pad34)") (class "Default")
      (node (ref "U1") (pin "34") (pinfunction "ACBUS7_34") (pintype "bidirectional"))
    )
    (net (code "141") (name "unconnected-(U1-ADBUS7-Pad24)") (class "Default")
      (node (ref "U1") (pin "24") (pinfunction "ADBUS7_24") (pintype "bidirectional"))
    )
    (net (code "142") (name "unconnected-(U1-BCBUS0-Pad48)") (class "Default")
      (node (ref "U1") (pin "48") (pinfunction "BCBUS0_48") (pintype "bidirectional"))
    )
    (net (code "143") (name "unconnected-(U1-BCBUS1-Pad52)") (class "Default")
      (node (ref "U1") (pin "52") (pinfunction "BCBUS1_52") (pintype "bidirectional"))
    )
    (net (code "144") (name "unconnected-(U1-BCBUS2-Pad53)") (class "Default")
      (node (ref "U1") (pin "53") (pinfunction "BCBUS2_53") (pintype "bidirectional"))
    )
    (net (code "145") (name "unconnected-(U1-BCBUS3-Pad54)") (class "Default")
      (node (ref "U1") (pin "54") (pinfunction "BCBUS3_54") (pintype "bidirectional"))
    )
    (net (code "146") (name "unconnected-(U1-BCBUS4-Pad55)") (class "Default")
      (node (ref "U1") (pin "55") (pinfunction "BCBUS4_55") (pintype "bidirectional"))
    )
    (net (code "147") (name "unconnected-(U1-BCBUS5-Pad57)") (class "Default")
      (node (ref "U1") (pin "57") (pinfunction "BCBUS5_57") (pintype "bidirectional"))
    )
    (net (code "148") (name "unconnected-(U1-BCBUS6-Pad58)") (class "Default")
      (node (ref "U1") (pin "58") (pinfunction "BCBUS6_58") (pintype "bidirectional"))
    )
    (net (code "149") (name "unconnected-(U1-BCBUS7-Pad59)") (class "Default")
      (node (ref "U1") (pin "59") (pinfunction "BCBUS7_59") (pintype "bidirectional"))
    )
    (net (code "150") (name "unconnected-(U1-BDBUS7-Pad46)") (class "Default")
      (node (ref "U1") (pin "46") (pinfunction "BDBUS7_46") (pintype "bidirectional"))
    )
    (net (code "151") (name "unconnected-(U1-EECLK-Pad62)") (class "Default")
      (node (ref "U1") (pin "62") (pinfunction "EECLK_62") (pintype "bidirectional"))
    )
    (net (code "152") (name "unconnected-(U1-EECS-Pad63)") (class "Default")
      (node (ref "U1") (pin "63") (pinfunction "EECS_63") (pintype "bidirectional"))
    )
    (net (code "153") (name "unconnected-(U1-EEDATA-Pad61)") (class "Default")
      (node (ref "U1") (pin "61") (pinfunction "EEDATA_61") (pintype "bidirectional"))
    )
    (net (code "154") (name "unconnected-(U1-PWRENN-Pad60)") (class "Default")
      (node (ref "U1") (pin "60") (pinfunction "PWRENN_60") (pintype "bidirectional"))
    )
    (net (code "155") (name "unconnected-(U1-SUSPENDN-Pad36)") (class "Default")
      (node (ref "U1") (pin "36") (pinfunction "SUSPENDN_36") (pintype "bidirectional"))
    )
    (net (code "156") (name "unconnected-(U2-INVAL-Pad21)") (class "Default")
      (node (ref "U2") (pin "21") (pinfunction "INVAL_21") (pintype "output"))
    )
    (net (code "157") (name "unconnected-(U2-ROUT2B-Pad20)") (class "Default")
      (node (ref "U2") (pin "20") (pinfunction "ROUT2B_20") (pintype "output"))
    )
    (net (code "158") (name "unconnected-(U2-ROUT5-Pad15)") (class "Default")
      (node (ref "U2") (pin "15") (pinfunction "ROUT5_15") (pintype "output"))
    )
    (net (code "159") (name "unconnected-(U3-INVAL-Pad21)") (class "Default")
      (node (ref "U3") (pin "21") (pinfunction "INVAL_21") (pintype "output"))
    )
    (net (code "160") (name "unconnected-(U3-ROUT2B-Pad20)") (class "Default")
      (node (ref "U3") (pin "20") (pinfunction "ROUT2B_20") (pintype "output"))
    )
    (net (code "161") (name "unconnected-(U3-ROUT5-Pad15)") (class "Default")
      (node (ref "U3") (pin "15") (pinfunction "ROUT5_15") (pintype "output"))
    )
    (net (code "162") (name "unconnected-(U4-GPIN0-Pad26)") (class "Default")
      (node (ref "U4") (pin "26") (pinfunction "GPIN0_26") (pintype "input"))
    )
    (net (code "163") (name "unconnected-(U4-GPIN1-Pad27)") (class "Default")
      (node (ref "U4") (pin "27") (pinfunction "GPIN1_27") (pintype "input"))
    )
    (net (code "164") (name "unconnected-(U4-GPIN2-Pad28)") (class "Default")
      (node (ref "U4") (pin "28") (pinfunction "GPIN2_28") (pintype "input"))
    )
    (net (code "165") (name "unconnected-(U4-GPIN3-Pad29)") (class "Default")
      (node (ref "U4") (pin "29") (pinfunction "GPIN3_29") (pintype "input"))
    )
    (net (code "166") (name "unconnected-(U4-GPIN4-Pad30)") (class "Default")
      (node (ref "U4") (pin "30") (pinfunction "GPIN4_30") (pintype "input"))
    )
    (net (code "167") (name "unconnected-(U4-GPIN5-Pad31)") (class "Default")
      (node (ref "U4") (pin "31") (pinfunction "GPIN5_31") (pintype "input"))
    )
    (net (code "168") (name "unconnected-(U4-GPIN6-Pad32)") (class "Default")
      (node (ref "U4") (pin "32") (pinfunction "GPIN6_32") (pintype "input"))
    )
    (net (code "169") (name "unconnected-(U4-GPIN7-Pad1)") (class "Default")
      (node (ref "U4") (pin "1") (pinfunction "GPIN7_1") (pintype "input"))
    )
    (net (code "170") (name "unconnected-(U4-GPOUT0-Pad4)") (class "Default")
      (node (ref "U4") (pin "4") (pinfunction "GPOUT0_4") (pintype "output"))
    )
    (net (code "171") (name "unconnected-(U4-GPOUT1-Pad5)") (class "Default")
      (node (ref "U4") (pin "5") (pinfunction "GPOUT1_5") (pintype "output"))
    )
    (net (code "172") (name "unconnected-(U4-GPOUT2-Pad6)") (class "Default")
      (node (ref "U4") (pin "6") (pinfunction "GPOUT2_6") (pintype "output"))
    )
    (net (code "173") (name "unconnected-(U4-GPOUT3-Pad7)") (class "Default")
      (node (ref "U4") (pin "7") (pinfunction "GPOUT3_7") (pintype "output"))
    )
    (net (code "174") (name "unconnected-(U4-GPOUT4-Pad8)") (class "Default")
      (node (ref "U4") (pin "8") (pinfunction "GPOUT4_8") (pintype "output"))
    )
    (net (code "175") (name "unconnected-(U4-GPOUT5-Pad9)") (class "Default")
      (node (ref "U4") (pin "9") (pinfunction "GPOUT5_9") (pintype "output"))
    )
    (net (code "176") (name "unconnected-(U4-GPOUT6-Pad10)") (class "Default")
      (node (ref "U4") (pin "10") (pinfunction "GPOUT6_10") (pintype "output"))
    )
    (net (code "177") (name "unconnected-(U4-GPOUT7-Pad11)") (class "Default")
      (node (ref "U4") (pin "11") (pinfunction "GPOUT7_11") (pintype "output"))
    )
    (net (code "178") (name "unconnected-(U5-EN-Pad9)") (class "Default")
      (node (ref "U5") (pin "9") (pinfunction "EN_9") (pintype "input"))
    )
    (net (code "179") (name "unconnected-(U5-PG-Pad8)") (class "Default")
      (node (ref "U5") (pin "8") (pinfunction "PG_8") (pintype "open_collector"))
    )
    (net (code "180") (name "unconnected-(U6-EN-Pad3)") (class "Default")
      (node (ref "U6") (pin "3") (pinfunction "EN_3") (pintype "input"))
    )
    (net (code "181") (name "unconnected-(U6-NC-Pad4)") (class "Default")
      (node (ref "U6") (pin "4") (pinfunction "NC_4") (pintype "no_connect"))
    )
  )
)
